# SLT3-PAY-1Q2T_P2.net
KiCad netlist of a schematic drawn in Altium Designer
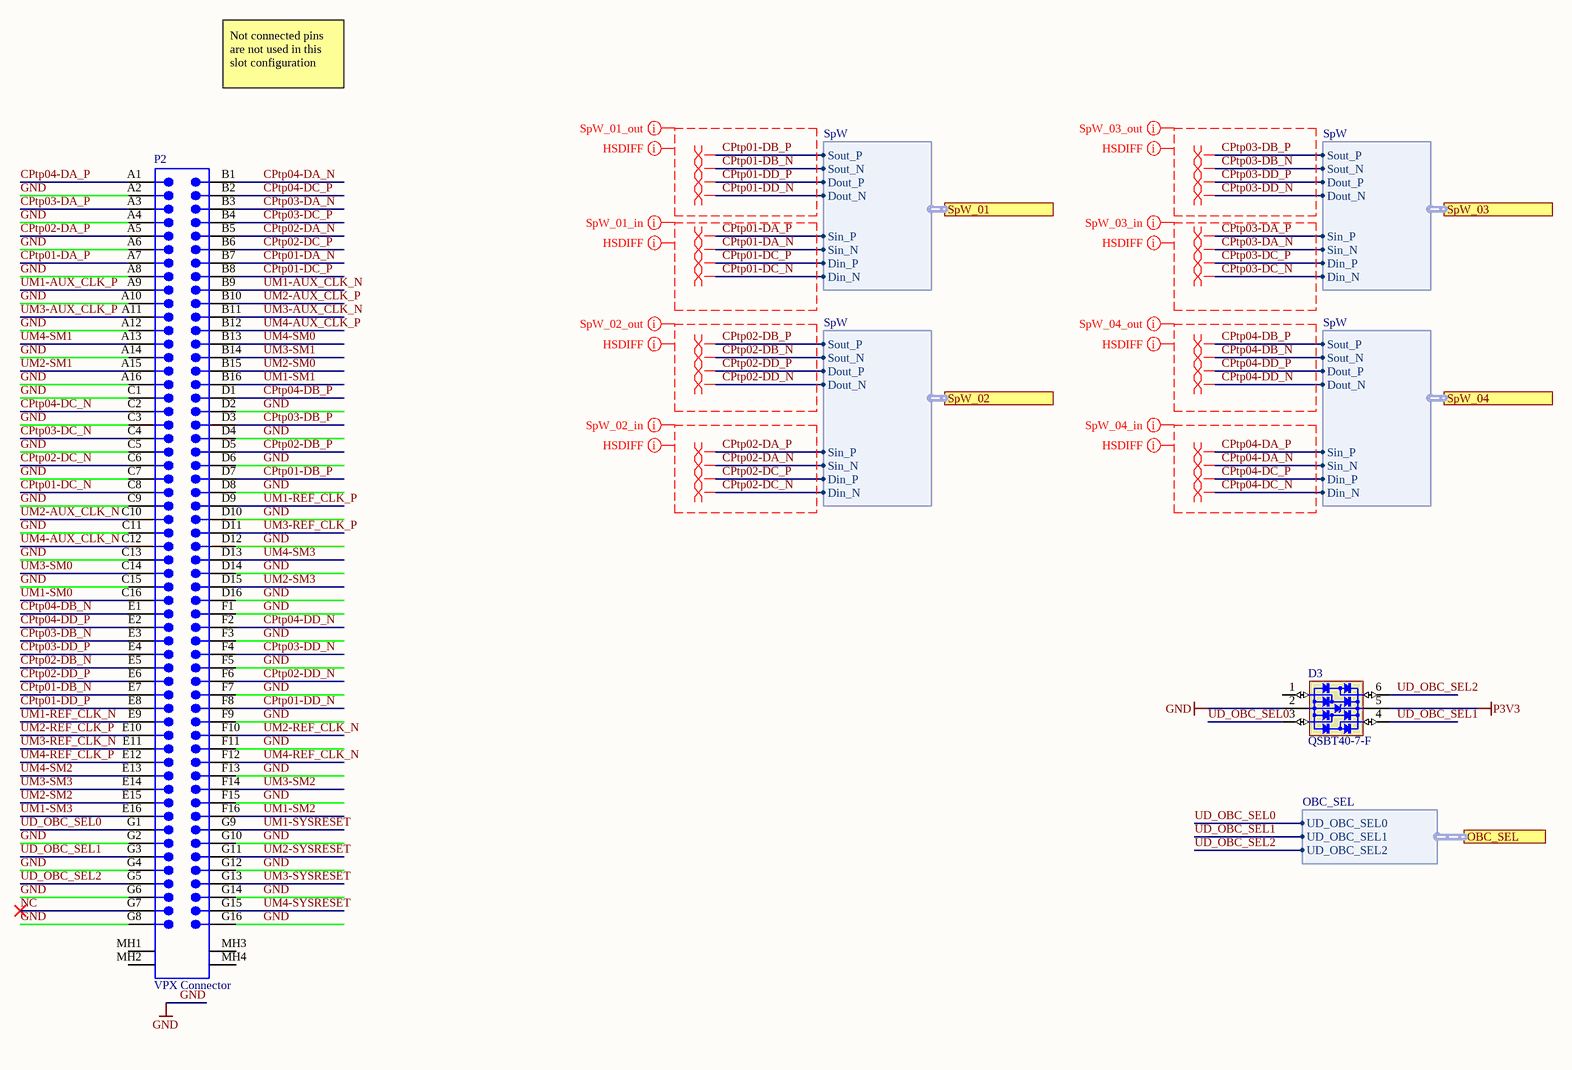
[diagram p0: SLT3-PAY-1Q2T_P2.SchDoc]

(export (version "E")
  (design (tool "Eeschema 10.0.6"))
  (components
    (comp (ref "D3")
      (value "QSBT40-7-F")
      (footprint "SOT65P210X110-6N")
      (libsource (lib "LIBRARY_SCH") (part "D_TVS_QSBT40-7-F"))
    )
    (comp (ref "P2")
      (value "VPX Connector")
      (footprint "BTB1-8-4H112M")
      (description "Ruggedized Board-to-Board Connector, Right Angle, 7-Row, Pitch 1.8mm, 112-Position")
      (fields (field (name "MANUFACTURER") "TE") (field (name "MANUFACTURER PART NUMBER") "2102771-1"))
      (libsource (lib "SVPX") (part "2102771-1"))
    )
  )
  (nets
    (net (code "3") (name "/CPtp01-DA_N") (class "Default")
      (node (ref "P2") (pin "B7") (pinfunction "B7_B7") (pintype "passive"))
    )
    (net (code "4") (name "/CPtp01-DA_P") (class "Default")
      (node (ref "P2") (pin "A7") (pinfunction "A7_A7") (pintype "passive"))
    )
    (net (code "5") (name "/CPtp01-DB_N") (class "Default")
      (node (ref "P2") (pin "E7") (pinfunction "E7_E7") (pintype "passive"))
    )
    (net (code "6") (name "/CPtp01-DB_P") (class "Default")
      (node (ref "P2") (pin "D7") (pinfunction "D7_D7") (pintype "passive"))
    )
    (net (code "7") (name "/CPtp01-DC_N") (class "Default")
      (node (ref "P2") (pin "C8") (pinfunction "C8_C8") (pintype "passive"))
    )
    (net (code "8") (name "/CPtp01-DC_P") (class "Default")
      (node (ref "P2") (pin "B8") (pinfunction "B8_B8") (pintype "passive"))
    )
    (net (code "9") (name "/CPtp01-DD_N") (class "Default")
      (node (ref "P2") (pin "F8") (pinfunction "F8_F8") (pintype "passive"))
    )
    (net (code "10") (name "/CPtp01-DD_P") (class "Default")
      (node (ref "P2") (pin "E8") (pinfunction "E8_E8") (pintype "passive"))
    )
    (net (code "11") (name "/CPtp02-DA_N") (class "Default")
      (node (ref "P2") (pin "B5") (pinfunction "B5_B5") (pintype "passive"))
    )
    (net (code "12") (name "/CPtp02-DA_P") (class "Default")
      (node (ref "P2") (pin "A5") (pinfunction "A5_A5") (pintype "passive"))
    )
    (net (code "13") (name "/CPtp02-DB_N") (class "Default")
      (node (ref "P2") (pin "E5") (pinfunction "E5_E5") (pintype "passive"))
    )
    (net (code "14") (name "/CPtp02-DB_P") (class "Default")
      (node (ref "P2") (pin "D5") (pinfunction "D5_D5") (pintype "passive"))
    )
    (net (code "15") (name "/CPtp02-DC_N") (class "Default")
      (node (ref "P2") (pin "C6") (pinfunction "C6_C6") (pintype "passive"))
    )
    (net (code "16") (name "/CPtp02-DC_P") (class "Default")
      (node (ref "P2") (pin "B6") (pinfunction "B6_B6") (pintype "passive"))
    )
    (net (code "17") (name "/CPtp02-DD_N") (class "Default")
      (node (ref "P2") (pin "F6") (pinfunction "F6_F6") (pintype "passive"))
    )
    (net (code "18") (name "/CPtp02-DD_P") (class "Default")
      (node (ref "P2") (pin "E6") (pinfunction "E6_E6") (pintype "passive"))
    )
    (net (code "19") (name "/CPtp03-DA_N") (class "Default")
      (node (ref "P2") (pin "B3") (pinfunction "B3_B3") (pintype "passive"))
    )
    (net (code "20") (name "/CPtp03-DA_P") (class "Default")
      (node (ref "P2") (pin "A3") (pinfunction "A3_A3") (pintype "passive"))
    )
    (net (code "21") (name "/CPtp03-DB_N") (class "Default")
      (node (ref "P2") (pin "E3") (pinfunction "E3_E3") (pintype "passive"))
    )
    (net (code "22") (name "/CPtp03-DB_P") (class "Default")
      (node (ref "P2") (pin "D3") (pinfunction "D3_D3") (pintype "passive"))
    )
    (net (code "23") (name "/CPtp03-DC_N") (class "Default")
      (node (ref "P2") (pin "C4") (pinfunction "C4_C4") (pintype "passive"))
    )
    (net (code "24") (name "/CPtp03-DC_P") (class "Default")
      (node (ref "P2") (pin "B4") (pinfunction "B4_B4") (pintype "passive"))
    )
    (net (code "25") (name "/CPtp03-DD_N") (class "Default")
      (node (ref "P2") (pin "F4") (pinfunction "F4_F4") (pintype "passive"))
    )
    (net (code "26") (name "/CPtp03-DD_P") (class "Default")
      (node (ref "P2") (pin "E4") (pinfunction "E4_E4") (pintype "passive"))
    )
    (net (code "27") (name "/CPtp04-DA_N") (class "Default")
      (node (ref "P2") (pin "B1") (pinfunction "B1_B1") (pintype "passive"))
    )
    (net (code "28") (name "/CPtp04-DA_P") (class "Default")
      (node (ref "P2") (pin "A1") (pinfunction "A1_A1") (pintype "passive"))
    )
    (net (code "29") (name "/CPtp04-DB_N") (class "Default")
      (node (ref "P2") (pin "E1") (pinfunction "E1_E1") (pintype "passive"))
    )
    (net (code "30") (name "/CPtp04-DB_P") (class "Default")
      (node (ref "P2") (pin "D1") (pinfunction "D1_D1") (pintype "passive"))
    )
    (net (code "31") (name "/CPtp04-DC_N") (class "Default")
      (node (ref "P2") (pin "C2") (pinfunction "C2_C2") (pintype "passive"))
    )
    (net (code "32") (name "/CPtp04-DC_P") (class "Default")
      (node (ref "P2") (pin "B2") (pinfunction "B2_B2") (pintype "passive"))
    )
    (net (code "33") (name "/CPtp04-DD_N") (class "Default")
      (node (ref "P2") (pin "F2") (pinfunction "F2_F2") (pintype "passive"))
    )
    (net (code "34") (name "/CPtp04-DD_P") (class "Default")
      (node (ref "P2") (pin "E2") (pinfunction "E2_E2") (pintype "passive"))
    )
    (net (code "35") (name "/NC") (class "Default")
      (node (ref "P2") (pin "G7") (pinfunction "G7_G7") (pintype "passive+no_connect"))
    )
    (net (code "36") (name "/UD_OBC_SEL0") (class "Default")
      (node (ref "D3") (pin "3") (pinfunction "I/O2_3") (pintype "bidirectional"))
      (node (ref "P2") (pin "G1") (pinfunction "G1_G1") (pintype "passive"))
    )
    (net (code "37") (name "/UD_OBC_SEL1") (class "Default")
      (node (ref "D3") (pin "4") (pinfunction "I/O3_4") (pintype "bidirectional"))
      (node (ref "P2") (pin "G3") (pinfunction "G3_G3") (pintype "passive"))
    )
    (net (code "38") (name "/UD_OBC_SEL2") (class "Default")
      (node (ref "D3") (pin "6") (pinfunction "I/O4_6") (pintype "bidirectional"))
      (node (ref "P2") (pin "G5") (pinfunction "G5_G5") (pintype "passive"))
    )
    (net (code "39") (name "/UM1-AUX_CLK_N") (class "Default")
      (node (ref "P2") (pin "B9") (pinfunction "B9_B9") (pintype "passive"))
    )
    (net (code "40") (name "/UM1-AUX_CLK_P") (class "Default")
      (node (ref "P2") (pin "A9") (pinfunction "A9_A9") (pintype "passive"))
    )
    (net (code "41") (name "/UM1-REF_CLK_N") (class "Default")
      (node (ref "P2") (pin "E9") (pinfunction "E9_E9") (pintype "passive"))
    )
    (net (code "42") (name "/UM1-REF_CLK_P") (class "Default")
      (node (ref "P2") (pin "D9") (pinfunction "D9_D9") (pintype "passive"))
    )
    (net (code "43") (name "/UM1-SM0") (class "Default")
      (node (ref "P2") (pin "C16") (pinfunction "C16_C16") (pintype "passive"))
    )
    (net (code "44") (name "/UM1-SM1") (class "Default")
      (node (ref "P2") (pin "B16") (pinfunction "B16_B16") (pintype "passive"))
    )
    (net (code "45") (name "/UM1-SM2") (class "Default")
      (node (ref "P2") (pin "F16") (pinfunction "F16_F16") (pintype "passive"))
    )
    (net (code "46") (name "/UM1-SM3") (class "Default")
      (node (ref "P2") (pin "E16") (pinfunction "E16_E16") (pintype "passive"))
    )
    (net (code "47") (name "/UM1-SYSRESET") (class "Default")
      (node (ref "P2") (pin "G9") (pinfunction "G9_G9") (pintype "passive"))
    )
    (net (code "48") (name "/UM2-AUX_CLK_N") (class "Default")
      (node (ref "P2") (pin "C10") (pinfunction "C10_C10") (pintype "passive"))
    )
    (net (code "49") (name "/UM2-AUX_CLK_P") (class "Default")
      (node (ref "P2") (pin "B10") (pinfunction "B10_B10") (pintype "passive"))
    )
    (net (code "50") (name "/UM2-REF_CLK_N") (class "Default")
      (node (ref "P2") (pin "F10") (pinfunction "F10_F10") (pintype "passive"))
    )
    (net (code "51") (name "/UM2-REF_CLK_P") (class "Default")
      (node (ref "P2") (pin "E10") (pinfunction "E10_E10") (pintype "passive"))
    )
    (net (code "52") (name "/UM2-SM0") (class "Default")
      (node (ref "P2") (pin "B15") (pinfunction "B15_B15") (pintype "passive"))
    )
    (net (code "53") (name "/UM2-SM1") (class "Default")
      (node (ref "P2") (pin "A15") (pinfunction "A15_A15") (pintype "passive"))
    )
    (net (code "54") (name "/UM2-SM2") (class "Default")
      (node (ref "P2") (pin "E15") (pinfunction "E15_E15") (pintype "passive"))
    )
    (net (code "55") (name "/UM2-SM3") (class "Default")
      (node (ref "P2") (pin "D15") (pinfunction "D15_D15") (pintype "passive"))
    )
    (net (code "56") (name "/UM2-SYSRESET") (class "Default")
      (node (ref "P2") (pin "G11") (pinfunction "G11_G11") (pintype "passive"))
    )
    (net (code "57") (name "/UM3-AUX_CLK_N") (class "Default")
      (node (ref "P2") (pin "B11") (pinfunction "B11_B11") (pintype "passive"))
    )
    (net (code "58") (name "/UM3-AUX_CLK_P") (class "Default")
      (node (ref "P2") (pin "A11") (pinfunction "A11_A11") (pintype "passive"))
    )
    (net (code "59") (name "/UM3-REF_CLK_N") (class "Default")
      (node (ref "P2") (pin "E11") (pinfunction "E11_E11") (pintype "passive"))
    )
    (net (code "60") (name "/UM3-REF_CLK_P") (class "Default")
      (node (ref "P2") (pin "D11") (pinfunction "D11_D11") (pintype "passive"))
    )
    (net (code "61") (name "/UM3-SM0") (class "Default")
      (node (ref "P2") (pin "C14") (pinfunction "C14_C14") (pintype "passive"))
    )
    (net (code "62") (name "/UM3-SM1") (class "Default")
      (node (ref "P2") (pin "B14") (pinfunction "B14_B14") (pintype "passive"))
    )
    (net (code "63") (name "/UM3-SM2") (class "Default")
      (node (ref "P2") (pin "F14") (pinfunction "F14_F14") (pintype "passive"))
    )
    (net (code "64") (name "/UM3-SM3") (class "Default")
      (node (ref "P2") (pin "E14") (pinfunction "E14_E14") (pintype "passive"))
    )
    (net (code "65") (name "/UM3-SYSRESET") (class "Default")
      (node (ref "P2") (pin "G13") (pinfunction "G13_G13") (pintype "passive"))
    )
    (net (code "66") (name "/UM4-AUX_CLK_N") (class "Default")
      (node (ref "P2") (pin "C12") (pinfunction "C12_C12") (pintype "passive"))
    )
    (net (code "67") (name "/UM4-AUX_CLK_P") (class "Default")
      (node (ref "P2") (pin "B12") (pinfunction "B12_B12") (pintype "passive"))
    )
    (net (code "68") (name "/UM4-REF_CLK_N") (class "Default")
      (node (ref "P2") (pin "F12") (pinfunction "F12_F12") (pintype "passive"))
    )
    (net (code "69") (name "/UM4-REF_CLK_P") (class "Default")
      (node (ref "P2") (pin "E12") (pinfunction "E12_E12") (pintype "passive"))
    )
    (net (code "70") (name "/UM4-SM0") (class "Default")
      (node (ref "P2") (pin "B13") (pinfunction "B13_B13") (pintype "passive"))
    )
    (net (code "71") (name "/UM4-SM1") (class "Default")
      (node (ref "P2") (pin "A13") (pinfunction "A13_A13") (pintype "passive"))
    )
    (net (code "72") (name "/UM4-SM2") (class "Default")
      (node (ref "P2") (pin "E13") (pinfunction "E13_E13") (pintype "passive"))
    )
    (net (code "73") (name "/UM4-SM3") (class "Default")
      (node (ref "P2") (pin "D13") (pinfunction "D13_D13") (pintype "passive"))
    )
    (net (code "74") (name "/UM4-SYSRESET") (class "Default")
      (node (ref "P2") (pin "G15") (pinfunction "G15_G15") (pintype "passive"))
    )
    (net (code "77") (name "GND") (class "Default")
      (node (ref "D3") (pin "2") (pinfunction "GND_2") (pintype "power_in"))
      (node (ref "P2") (pin "A10") (pinfunction "A10_A10") (pintype "passive"))
      (node (ref "P2") (pin "A12") (pinfunction "A12_A12") (pintype "passive"))
      (node (ref "P2") (pin "A14") (pinfunction "A14_A14") (pintype "passive"))
      (node (ref "P2") (pin "A16") (pinfunction "A16_A16") (pintype "passive"))
      (node (ref "P2") (pin "A2") (pinfunction "A2_A2") (pintype "passive"))
      (node (ref "P2") (pin "A4") (pinfunction "A4_A4") (pintype "passive"))
      (node (ref "P2") (pin "A6") (pinfunction "A6_A6") (pintype "passive"))
      (node (ref "P2") (pin "A8") (pinfunction "A8_A8") (pintype "passive"))
      (node (ref "P2") (pin "C1") (pinfunction "C1_C1") (pintype "passive"))
      (node (ref "P2") (pin "C11") (pinfunction "C11_C11") (pintype "passive"))
      (node (ref "P2") (pin "C13") (pinfunction "C13_C13") (pintype "passive"))
      (node (ref "P2") (pin "C15") (pinfunction "C15_C15") (pintype "passive"))
      (node (ref "P2") (pin "C3") (pinfunction "C3_C3") (pintype "passive"))
      (node (ref "P2") (pin "C5") (pinfunction "C5_C5") (pintype "passive"))
      (node (ref "P2") (pin "C7") (pinfunction "C7_C7") (pintype "passive"))
      (node (ref "P2") (pin "C9") (pinfunction "C9_C9") (pintype "passive"))
      (node (ref "P2") (pin "D10") (pinfunction "D10_D10") (pintype "passive"))
      (node (ref "P2") (pin "D12") (pinfunction "D12_D12") (pintype "passive"))
      (node (ref "P2") (pin "D14") (pinfunction "D14_D14") (pintype "passive"))
      (node (ref "P2") (pin "D16") (pinfunction "D16_D16") (pintype "passive"))
      (node (ref "P2") (pin "D2") (pinfunction "D2_D2") (pintype "passive"))
      (node (ref "P2") (pin "D4") (pinfunction "D4_D4") (pintype "passive"))
      (node (ref "P2") (pin "D6") (pinfunction "D6_D6") (pintype "passive"))
      (node (ref "P2") (pin "D8") (pinfunction "D8_D8") (pintype "passive"))
      (node (ref "P2") (pin "F1") (pinfunction "F1_F1") (pintype "passive"))
      (node (ref "P2") (pin "F11") (pinfunction "F11_F11") (pintype "passive"))
      (node (ref "P2") (pin "F13") (pinfunction "F13_F13") (pintype "passive"))
      (node (ref "P2") (pin "F15") (pinfunction "F15_F15") (pintype "passive"))
      (node (ref "P2") (pin "F3") (pinfunction "F3_F3") (pintype "passive"))
      (node (ref "P2") (pin "F5") (pinfunction "F5_F5") (pintype "passive"))
      (node (ref "P2") (pin "F7") (pinfunction "F7_F7") (pintype "passive"))
      (node (ref "P2") (pin "F9") (pinfunction "F9_F9") (pintype "passive"))
      (node (ref "P2") (pin "G10") (pinfunction "G10_G10") (pintype "passive"))
      (node (ref "P2") (pin "G12") (pinfunction "G12_G12") (pintype "passive"))
      (node (ref "P2") (pin "G14") (pinfunction "G14_G14") (pintype "passive"))
      (node (ref "P2") (pin "G16") (pinfunction "G16_G16") (pintype "passive"))
      (node (ref "P2") (pin "G2") (pinfunction "G2_G2") (pintype "passive"))
      (node (ref "P2") (pin "G4") (pinfunction "G4_G4") (pintype "passive"))
      (node (ref "P2") (pin "G6") (pinfunction "G6_G6") (pintype "passive"))
      (node (ref "P2") (pin "G8") (pinfunction "G8_G8") (pintype "passive"))
    )
    (net (code "78") (name "P3V3") (class "Default")
      (node (ref "D3") (pin "5") (pinfunction "VBUS_5") (pintype "power_in"))
    )
    (net (code "79") (name "unconnected-(D3-I{slash}O1-Pad1)") (class "Default")
      (node (ref "D3") (pin "1") (pinfunction "I/O1_1") (pintype "bidirectional"))
    )
    (net (code "80") (name "unconnected-(P2-PadMH1)") (class "Default")
      (node (ref "P2") (pin "MH1") (pinfunction "MH1_MH1") (pintype "passive"))
    )
    (net (code "81") (name "unconnected-(P2-PadMH2)") (class "Default")
      (node (ref "P2") (pin "MH2") (pinfunction "MH2_MH2") (pintype "passive"))
    )
    (net (code "82") (name "unconnected-(P2-PadMH3)") (class "Default")
      (node (ref "P2") (pin "MH3") (pinfunction "MH3_MH3") (pintype "passive"))
    )
    (net (code "83") (name "unconnected-(P2-PadMH4)") (class "Default")
      (node (ref "P2") (pin "MH4") (pinfunction "MH4_MH4") (pintype "passive"))
    )
  )
)
